# SDCARD.net
KiCad netlist of a schematic drawn in Altium Designer
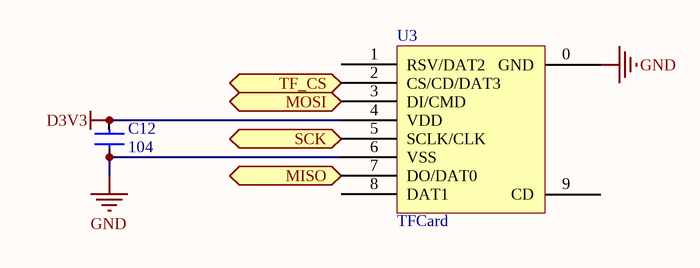
[diagram p0: SDCARD.SchDoc]

(export (version "E")
  (design (tool "Eeschema 10.0.6"))
  (components
    (comp (ref "C12")
      (value "104")
      (footprint "0603C")
      (description "普通小电容")
      (libsource (lib "lib_AD") (part "CAP"))
    )
    (comp (ref "U3") (value "TFCard") (footprint "TF-2") (libsource (lib "lib_AD") (part "TFCARD")))
  )
  (nets
    (net (code "1") (name "/MISO") (class "Default")
      (node (ref "U3") (pin "7") (pinfunction "DO/DAT0_7") (pintype "passive"))
    )
    (net (code "2") (name "/MOSI") (class "Default")
      (node (ref "U3") (pin "3") (pinfunction "DI/CMD_3") (pintype "passive"))
    )
    (net (code "3") (name "/SCK") (class "Default")
      (node (ref "U3") (pin "5") (pinfunction "SCLK/CLK_5") (pintype "passive"))
    )
    (net (code "4") (name "/TF_CS") (class "Default")
      (node (ref "U3") (pin "2") (pinfunction "CS/CD/DAT3_2") (pintype "passive"))
    )
    (net (code "5") (name "D3V3") (class "Default")
      (node (ref "C12") (pin "1") (pinfunction "1_1") (pintype "passive"))
      (node (ref "U3") (pin "4") (pinfunction "VDD_4") (pintype "passive"))
    )
    (net (code "6") (name "GND") (class "Default")
      (node (ref "C12") (pin "2") (pinfunction "2_2") (pintype "passive"))
      (node (ref "U3") (pin "0") (pinfunction "GND_0") (pintype "passive"))
      (node (ref "U3") (pin "6") (pinfunction "VSS_6") (pintype "passive"))
    )
    (net (code "7") (name "unconnected-(U3-CD-Pad9)") (class "Default")
      (node (ref "U3") (pin "9") (pinfunction "CD_9") (pintype "passive"))
    )
    (net (code "8") (name "unconnected-(U3-DAT1-Pad8)") (class "Default")
      (node (ref "U3") (pin "8") (pinfunction "DAT1_8") (pintype "passive"))
    )
    (net (code "9") (name "unconnected-(U3-RSV{slash}DAT2-Pad1)") (class "Default")
      (node (ref "U3") (pin "1") (pinfunction "RSV/DAT2_1") (pintype "passive"))
    )
  )
)
